# xiao-rp2040.net
KiCad netlist of a schematic drawn in EAGLE
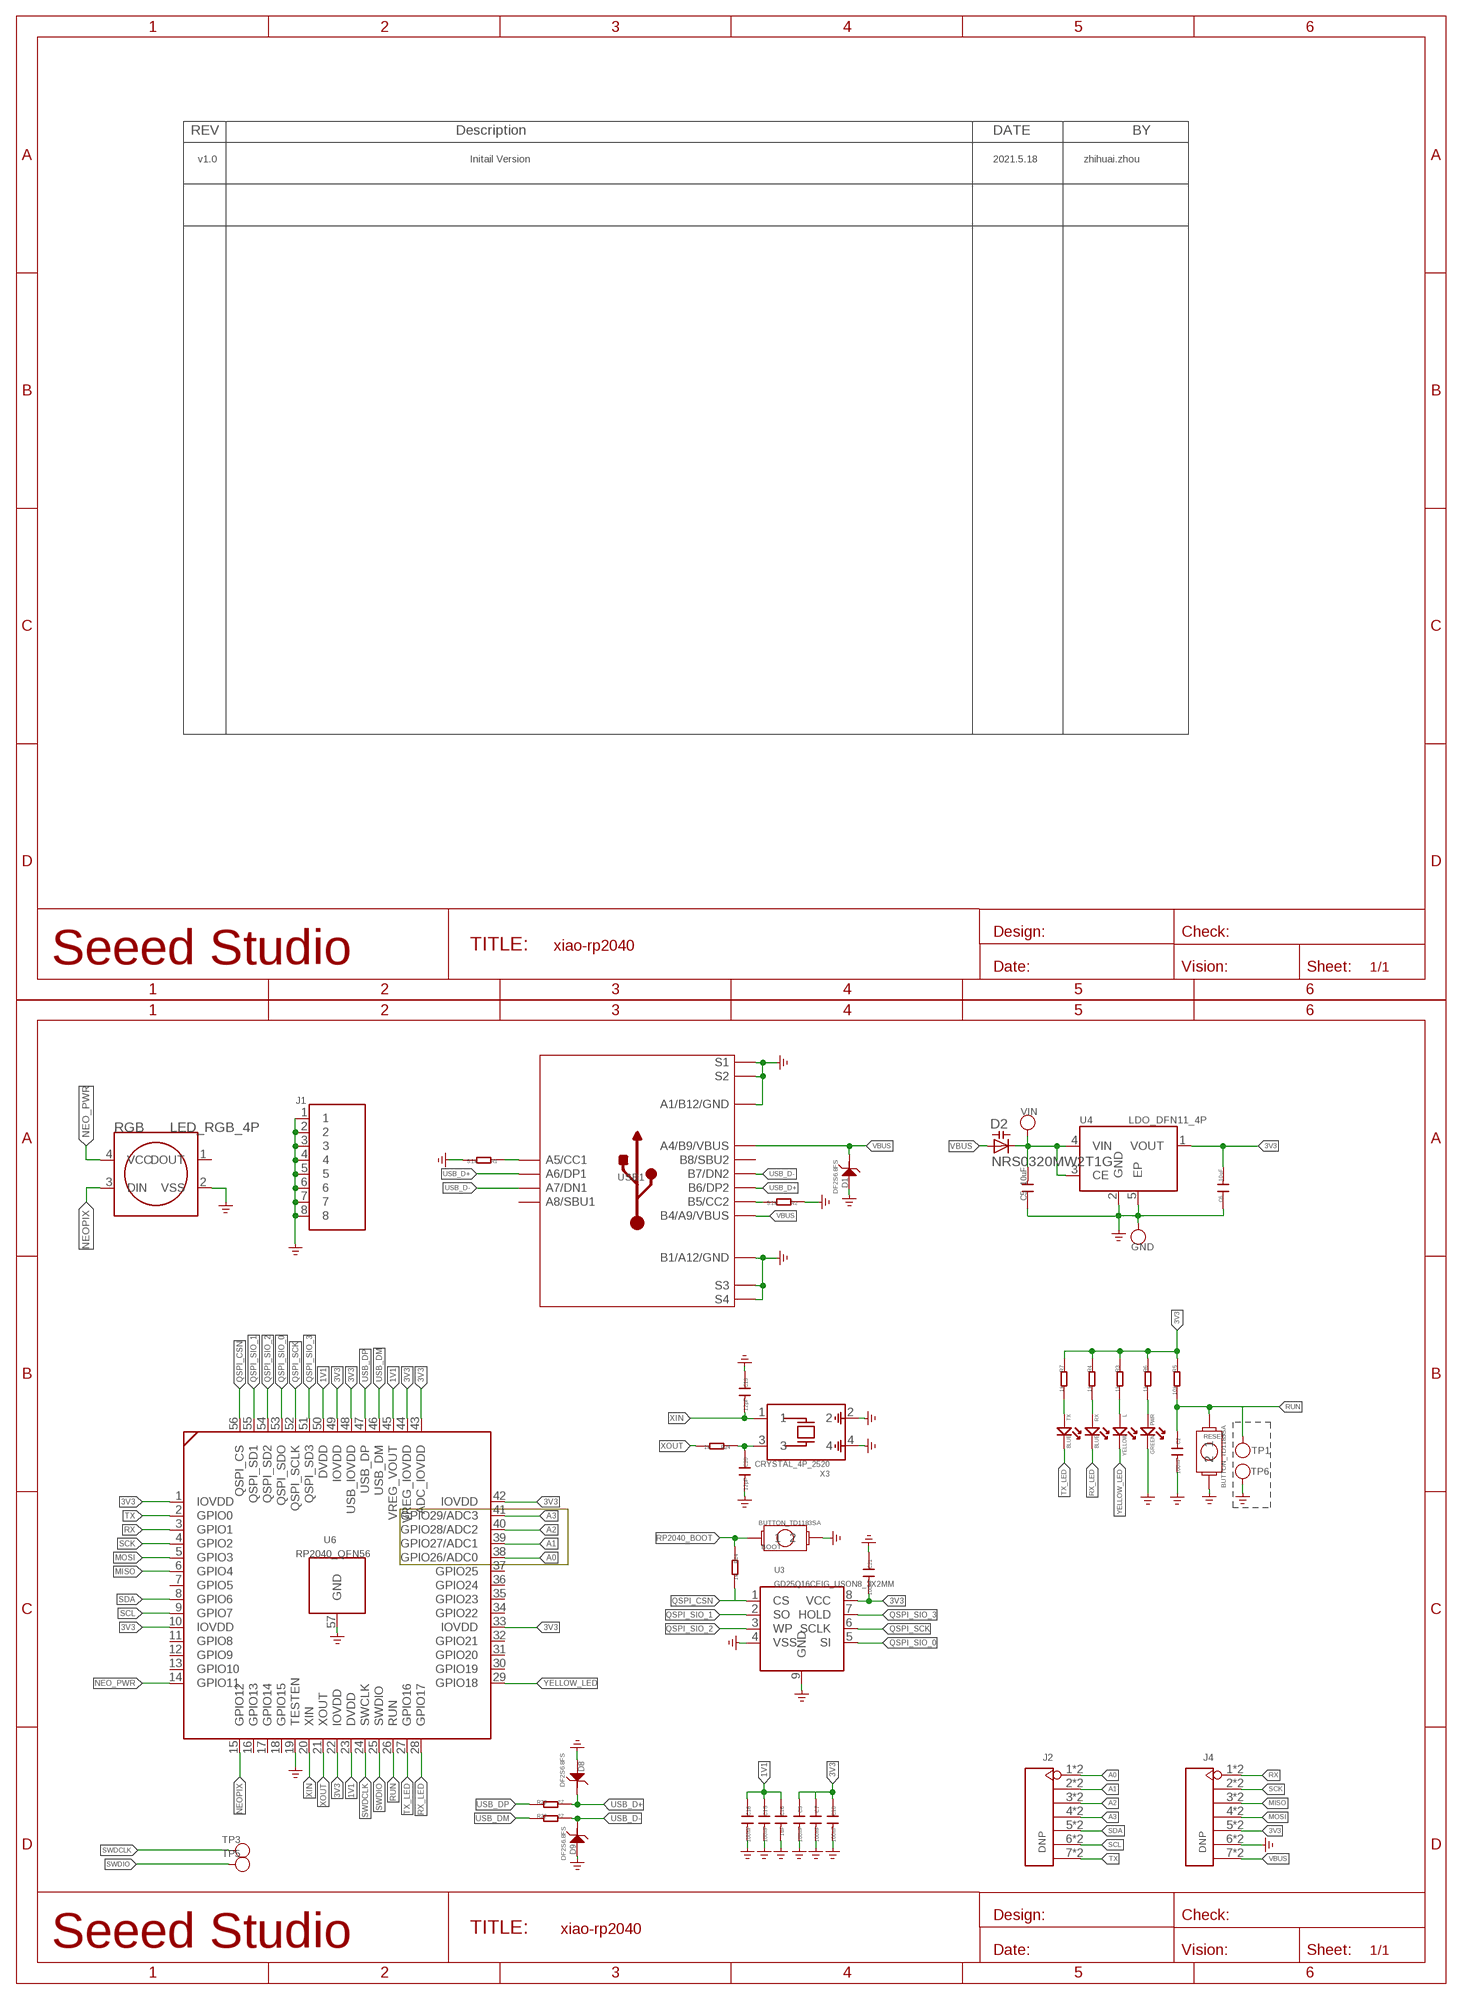
[diagram p0: schematic, sheet 1]

(export (version "E")
  (design (tool "Eeschema 10.0.6"))
  (components
    (comp (ref "BOOT")
      (value "BUTTON_TD1183SA")
      (footprint "eagle-import:BUTTON_TD1183SA")
      (libsource (lib "eagle-import") (part "BUTTON_TD1183SA"))
    )
    (comp (ref "C2")
      (value "100nF")
      (footprint "eagle-import:0201_NORMAL_NOSILK")
      (libsource (lib "eagle-import") (part "CAP{backslash}0201NNS"))
    )
    (comp (ref "C3")
      (value "100nF")
      (footprint "eagle-import:0201_NORMAL_NOSILK")
      (libsource (lib "eagle-import") (part "CAP{backslash}0201NNS"))
    )
    (comp (ref "C5")
      (value "10uF")
      (footprint "eagle-import:C0402")
      (libsource (lib "eagle-import") (part "C-0402"))
    )
    (comp (ref "C6")
      (value "10uF")
      (footprint "eagle-import:C0402")
      (libsource (lib "eagle-import") (part "C-0402"))
    )
    (comp (ref "C7")
      (value "100nF")
      (footprint "eagle-import:0201_NORMAL_NOSILK")
      (libsource (lib "eagle-import") (part "CAP{backslash}0201NNS"))
    )
    (comp (ref "C10")
      (value "100nF")
      (footprint "eagle-import:0201_NORMAL_NOSILK")
      (libsource (lib "eagle-import") (part "CAP{backslash}0201NNS"))
    )
    (comp (ref "C15")
      (value "100nF")
      (footprint "eagle-import:0201_NORMAL_NOSILK")
      (libsource (lib "eagle-import") (part "CAP{backslash}0201NNS"))
    )
    (comp (ref "C16")
      (value "1uF")
      (footprint "eagle-import:0201_NORMAL_NOSILK")
      (libsource (lib "eagle-import") (part "CAP{backslash}0201NNS"))
    )
    (comp (ref "C18")
      (value "100nF")
      (footprint "eagle-import:0201_NORMAL_NOSILK")
      (libsource (lib "eagle-import") (part "CAP{backslash}0201NNS"))
    )
    (comp (ref "C19")
      (value "12pF")
      (footprint "eagle-import:0201_NORMAL_NOSILK")
      (libsource (lib "eagle-import") (part "CAP{backslash}0201NNS"))
    )
    (comp (ref "C20")
      (value "12pF")
      (footprint "eagle-import:0201_NORMAL_NOSILK")
      (libsource (lib "eagle-import") (part "CAP{backslash}0201NNS"))
    )
    (comp (ref "C21")
      (value "100nF")
      (footprint "eagle-import:0201_NORMAL_NOSILK")
      (libsource (lib "eagle-import") (part "CAP{backslash}0201NNS"))
    )
    (comp (ref "D1")
      (value "DF2S6.8FS")
      (footprint "eagle-import:SOD-923")
      (libsource (lib "eagle-import") (part "D-ESD-2P'DF2S6.8FS'"))
    )
    (comp (ref "D2")
      (value "NRS0320MW2T1G")
      (footprint "eagle-import:SOD523")
      (libsource (lib "eagle-import") (part "DIODE_CAPACITANCE-SOD523"))
    )
    (comp (ref "D8")
      (value "DF2S6.8FS")
      (footprint "eagle-import:SOD-923")
      (libsource (lib "eagle-import") (part "D-ESD-2P'DF2S6.8FS'"))
    )
    (comp (ref "D9")
      (value "DF2S6.8FS")
      (footprint "eagle-import:SOD-923")
      (libsource (lib "eagle-import") (part "D-ESD-2P'DF2S6.8FS'"))
    )
    (comp (ref "GND")
      (value "TEST-POINT'4080'")
      (footprint "eagle-import:TP-80X40MIL")
      (libsource (lib "eagle-import") (part "TEST-POINT'4080'"))
    )
    (comp (ref "J1")
      (value "SHIELDING-COVER-XIAO_RP2040_PRD")
      (footprint "eagle-import:SHIELDING-COVER_XIAO_RP2040_PRD")
      (libsource (lib "eagle-import") (part "SHIELDING-COVER-XIAO_RP2040_PRD"))
    )
    (comp (ref "J2")
      (value "DNP")
      (footprint "eagle-import:H7-HALF-HOLE-2.54")
      (libsource (lib "eagle-import") (part "HEADER-7P-HALF-HOLE-2.54"))
    )
    (comp (ref "J4")
      (value "DNP")
      (footprint "eagle-import:H7-HALF-HOLE-2.54")
      (libsource (lib "eagle-import") (part "HEADER-7P-HALF-HOLE-2.54"))
    )
    (comp (ref "L")
      (value "YELLOW")
      (footprint "eagle-import:LED-0402")
      (libsource (lib "eagle-import") (part "LED-0402"))
    )
    (comp (ref "PWR")
      (value "GREEN")
      (footprint "eagle-import:LED-0402")
      (libsource (lib "eagle-import") (part "LED-0402"))
    )
    (comp (ref "R1")
      (value "5.1k")
      (footprint "eagle-import:R0201")
      (libsource (lib "eagle-import") (part "R-0201"))
    )
    (comp (ref "R2")
      (value "5.1k")
      (footprint "eagle-import:R0201")
      (libsource (lib "eagle-import") (part "R-0201"))
    )
    (comp (ref "R3")
      (value "1k")
      (footprint "eagle-import:R0201")
      (libsource (lib "eagle-import") (part "R-0201"))
    )
    (comp (ref "R4")
      (value "1k")
      (footprint "eagle-import:R0201")
      (libsource (lib "eagle-import") (part "R-0201"))
    )
    (comp (ref "R5")
      (value "10k")
      (footprint "eagle-import:R0201")
      (libsource (lib "eagle-import") (part "R-0201"))
    )
    (comp (ref "R6")
      (value "1k")
      (footprint "eagle-import:R0201")
      (libsource (lib "eagle-import") (part "R-0201"))
    )
    (comp (ref "R7")
      (value "1k")
      (footprint "eagle-import:R0201")
      (libsource (lib "eagle-import") (part "R-0201"))
    )
    (comp (ref "R14")
      (value "1k")
      (footprint "eagle-import:R0201")
      (libsource (lib "eagle-import") (part "R-0201"))
    )
    (comp (ref "R22")
      (value "27")
      (footprint "eagle-import:R0201")
      (libsource (lib "eagle-import") (part "R-0201"))
    )
    (comp (ref "R23")
      (value "27")
      (footprint "eagle-import:R0201")
      (libsource (lib "eagle-import") (part "R-0201"))
    )
    (comp (ref "R24")
      (value "1k")
      (footprint "eagle-import:R0201")
      (libsource (lib "eagle-import") (part "R-0201"))
    )
    (comp (ref "RESET")
      (value "BUTTON_TD1183SA")
      (footprint "eagle-import:BUTTON_TD1183SA")
      (libsource (lib "eagle-import") (part "BUTTON_TD1183SA"))
    )
    (comp (ref "RGB")
      (value "LED_RGB_4P")
      (footprint "eagle-import:LED_RGB_2427")
      (libsource (lib "eagle-import") (part "LED_RGB_4P"))
    )
    (comp (ref "RX")
      (value "BLUE")
      (footprint "eagle-import:LED-0402")
      (libsource (lib "eagle-import") (part "LED-0402"))
    )
    (comp (ref "TP1")
      (value "TEST-POINT'4545'")
      (footprint "eagle-import:TP-D45MIL")
      (fields (field (name "PARTNO") "DNP"))
      (libsource (lib "eagle-import") (part "TEST-POINT'4545'"))
    )
    (comp (ref "TP3")
      (value "TEST-POINT'4545'")
      (footprint "eagle-import:TP-D45MIL")
      (fields (field (name "PARTNO") "DNP"))
      (libsource (lib "eagle-import") (part "TEST-POINT'4545'"))
    )
    (comp (ref "TP5")
      (value "TEST-POINT'4545'")
      (footprint "eagle-import:TP-D45MIL")
      (fields (field (name "PARTNO") "DNP"))
      (libsource (lib "eagle-import") (part "TEST-POINT'4545'"))
    )
    (comp (ref "TP6")
      (value "TEST-POINT'4545'")
      (footprint "eagle-import:TP-D45MIL")
      (fields (field (name "PARTNO") "DNP"))
      (libsource (lib "eagle-import") (part "TEST-POINT'4545'"))
    )
    (comp (ref "TX")
      (value "BLUE")
      (footprint "eagle-import:LED-0402")
      (libsource (lib "eagle-import") (part "LED-0402"))
    )
    (comp (ref "U3")
      (value "GD25Q16CEIG_USON8_3X2MM")
      (footprint "eagle-import:GD25Q16CEIG_USON8_3X2MM")
      (libsource (lib "eagle-import") (part "GD25Q16CEIG_USON8_3X2MM"))
    )
    (comp (ref "U4")
      (value "LDO_DFN11_4P")
      (footprint "eagle-import:LDO_DFN1_1_4P")
      (libsource (lib "eagle-import") (part "LDO_DFN11_4P"))
    )
    (comp (ref "U6")
      (value "RP2040_QFN56")
      (footprint "eagle-import:RP2040_QFN56")
      (libsource (lib "eagle-import") (part "RP2040_QFN56"))
    )
    (comp (ref "USB1")
      (value "USB2.0-TYPE-C")
      (footprint "eagle-import:USB2.0-TYPE-C")
      (libsource (lib "eagle-import") (part "USB2.0-TYPE-C"))
    )
    (comp (ref "VIN")
      (value "TEST-POINT'4080'")
      (footprint "eagle-import:TP-80X40MIL")
      (libsource (lib "eagle-import") (part "TEST-POINT'4080'"))
    )
    (comp (ref "X3")
      (value "CRYSTAL_4P_2520")
      (footprint "eagle-import:CRYSTAL_4P_2520")
      (libsource (lib "eagle-import") (part "CRYSTAL_4P_2520"))
    )
  )
  (nets
    (net (code "1") (name "1V1") (class "Default")
      (node (ref "C15") (pin "1") (pinfunction "1_1") (pintype "passive"))
      (node (ref "C16") (pin "1") (pinfunction "1_1") (pintype "passive"))
      (node (ref "C18") (pin "1") (pinfunction "1_1") (pintype "passive"))
      (node (ref "U6") (pin "23") (pinfunction "DVDD_23") (pintype "bidirectional"))
      (node (ref "U6") (pin "45") (pinfunction "VREG_VOUT_45") (pintype "bidirectional"))
      (node (ref "U6") (pin "50") (pinfunction "DVDD_50") (pintype "bidirectional"))
    )
    (net (code "2") (name "3V3") (class "Default")
      (node (ref "C10") (pin "1") (pinfunction "1_1") (pintype "passive"))
      (node (ref "C21") (pin "2") (pinfunction "2_2") (pintype "passive"))
      (node (ref "C3") (pin "1") (pinfunction "1_1") (pintype "passive"))
      (node (ref "C6") (pin "2") (pinfunction "2_2") (pintype "passive"))
      (node (ref "C7") (pin "1") (pinfunction "1_1") (pintype "passive"))
      (node (ref "J4") (pin "17") (pinfunction "5_17") (pintype "bidirectional"))
      (node (ref "J4") (pin "5") (pinfunction "5_5") (pintype "bidirectional"))
      (node (ref "R3") (pin "1") (pinfunction "1_1") (pintype "passive"))
      (node (ref "R4") (pin "1") (pinfunction "1_1") (pintype "passive"))
      (node (ref "R5") (pin "1") (pinfunction "1_1") (pintype "passive"))
      (node (ref "R6") (pin "1") (pinfunction "1_1") (pintype "passive"))
      (node (ref "R7") (pin "1") (pinfunction "1_1") (pintype "passive"))
      (node (ref "U3") (pin "8") (pinfunction "VCC_8") (pintype "bidirectional"))
      (node (ref "U4") (pin "1") (pinfunction "VOUT_1") (pintype "bidirectional"))
      (node (ref "U6") (pin "1") (pinfunction "IOVDD_1") (pintype "bidirectional"))
      (node (ref "U6") (pin "10") (pinfunction "IOVDD_10") (pintype "bidirectional"))
      (node (ref "U6") (pin "22") (pinfunction "IOVDD_22") (pintype "bidirectional"))
      (node (ref "U6") (pin "33") (pinfunction "IOVDD_33") (pintype "bidirectional"))
      (node (ref "U6") (pin "42") (pinfunction "IOVDD_42") (pintype "bidirectional"))
      (node (ref "U6") (pin "43") (pinfunction "ADC_IOVDD_43") (pintype "bidirectional"))
      (node (ref "U6") (pin "44") (pinfunction "VREG_IOVDD_44") (pintype "bidirectional"))
      (node (ref "U6") (pin "48") (pinfunction "USB_IOVDD_48") (pintype "bidirectional"))
      (node (ref "U6") (pin "49") (pinfunction "IOVDD_49") (pintype "bidirectional"))
    )
    (net (code "3") (name "A0") (class "Default")
      (node (ref "J2") (pin "1") (pinfunction "1_1") (pintype "bidirectional"))
      (node (ref "J2") (pin "13") (pinfunction "1_13") (pintype "bidirectional"))
      (node (ref "U6") (pin "38") (pinfunction "GPIO26/ADC0_38") (pintype "bidirectional"))
    )
    (net (code "4") (name "A1") (class "Default")
      (node (ref "J2") (pin "14") (pinfunction "2_14") (pintype "bidirectional"))
      (node (ref "J2") (pin "2") (pinfunction "2_2") (pintype "bidirectional"))
      (node (ref "U6") (pin "39") (pinfunction "GPIO27/ADC1_39") (pintype "bidirectional"))
    )
    (net (code "5") (name "A2") (class "Default")
      (node (ref "J2") (pin "15") (pinfunction "3_15") (pintype "bidirectional"))
      (node (ref "J2") (pin "3") (pinfunction "3_3") (pintype "bidirectional"))
      (node (ref "U6") (pin "40") (pinfunction "GPIO28/ADC2_40") (pintype "bidirectional"))
    )
    (net (code "6") (name "A3") (class "Default")
      (node (ref "J2") (pin "16") (pinfunction "4_16") (pintype "bidirectional"))
      (node (ref "J2") (pin "4") (pinfunction "4_4") (pintype "bidirectional"))
      (node (ref "U6") (pin "41") (pinfunction "GPIO29/ADC3_41") (pintype "bidirectional"))
    )
    (net (code "7") (name "GND_POWER") (class "Default")
      (node (ref "BOOT") (pin "2") (pinfunction "2_2") (pintype "bidirectional"))
      (node (ref "C10") (pin "2") (pinfunction "2_2") (pintype "passive"))
      (node (ref "C15") (pin "2") (pinfunction "2_2") (pintype "passive"))
      (node (ref "C16") (pin "2") (pinfunction "2_2") (pintype "passive"))
      (node (ref "C18") (pin "2") (pinfunction "2_2") (pintype "passive"))
      (node (ref "C19") (pin "1") (pinfunction "1_1") (pintype "passive"))
      (node (ref "C2") (pin "2") (pinfunction "2_2") (pintype "passive"))
      (node (ref "C20") (pin "2") (pinfunction "2_2") (pintype "passive"))
      (node (ref "C21") (pin "1") (pinfunction "1_1") (pintype "passive"))
      (node (ref "C3") (pin "2") (pinfunction "2_2") (pintype "passive"))
      (node (ref "C5") (pin "1") (pinfunction "1_1") (pintype "passive"))
      (node (ref "C6") (pin "1") (pinfunction "1_1") (pintype "passive"))
      (node (ref "C7") (pin "2") (pinfunction "2_2") (pintype "passive"))
      (node (ref "D1") (pin "2") (pinfunction "1_2") (pintype "bidirectional"))
      (node (ref "D8") (pin "2") (pinfunction "1_2") (pintype "bidirectional"))
      (node (ref "D9") (pin "2") (pinfunction "1_2") (pintype "bidirectional"))
      (node (ref "GND") (pin "1") (pinfunction "T_1") (pintype "bidirectional"))
      (node (ref "J1") (pin "1") (pinfunction "1_1") (pintype "bidirectional"))
      (node (ref "J1") (pin "2") (pinfunction "2_2") (pintype "bidirectional"))
      (node (ref "J1") (pin "3") (pinfunction "3_3") (pintype "bidirectional"))
      (node (ref "J1") (pin "4") (pinfunction "4_4") (pintype "bidirectional"))
      (node (ref "J1") (pin "5") (pinfunction "5_5") (pintype "bidirectional"))
      (node (ref "J1") (pin "6") (pinfunction "6_6") (pintype "bidirectional"))
      (node (ref "J1") (pin "7") (pinfunction "7_7") (pintype "bidirectional"))
      (node (ref "J1") (pin "8") (pinfunction "8_8") (pintype "bidirectional"))
      (node (ref "J4") (pin "18") (pinfunction "6_18") (pintype "bidirectional"))
      (node (ref "J4") (pin "6") (pinfunction "6_6") (pintype "bidirectional"))
      (node (ref "PWR") (pin "-") (pinfunction "-_-") (pintype "passive"))
      (node (ref "R1") (pin "2") (pinfunction "2_2") (pintype "passive"))
      (node (ref "R2") (pin "1") (pinfunction "1_1") (pintype "passive"))
      (node (ref "RESET") (pin "2") (pinfunction "2_2") (pintype "bidirectional"))
      (node (ref "RGB") (pin "2") (pinfunction "VSS_2") (pintype "bidirectional"))
      (node (ref "TP6") (pin "T") (pinfunction "T_T") (pintype "bidirectional"))
      (node (ref "U3") (pin "4") (pinfunction "VSS_4") (pintype "bidirectional"))
      (node (ref "U3") (pin "9") (pinfunction "GND_9") (pintype "bidirectional"))
      (node (ref "U4") (pin "2") (pinfunction "GND_2") (pintype "bidirectional"))
      (node (ref "U4") (pin "5") (pinfunction "EP_5") (pintype "bidirectional"))
      (node (ref "U6") (pin "19") (pinfunction "TESTEN_19") (pintype "bidirectional"))
      (node (ref "U6") (pin "57") (pinfunction "GND_57") (pintype "bidirectional"))
      (node (ref "USB1") (pin "A1_B12") (pinfunction "A1/B12/GND_A1_B12") (pintype "bidirectional"))
      (node (ref "USB1") (pin "B1_A12") (pinfunction "B1/A12/GND_B1_A12") (pintype "bidirectional"))
      (node (ref "USB1") (pin "S1") (pinfunction "S1_S1") (pintype "bidirectional"))
      (node (ref "USB1") (pin "S2") (pinfunction "S2_S2") (pintype "bidirectional"))
      (node (ref "USB1") (pin "S3") (pinfunction "S3_S3") (pintype "bidirectional"))
      (node (ref "USB1") (pin "S4") (pinfunction "S4_S4") (pintype "bidirectional"))
      (node (ref "USB1") (pin "S5") (pinfunction "S1_S5") (pintype "bidirectional"))
      (node (ref "USB1") (pin "S6") (pinfunction "S2_S6") (pintype "bidirectional"))
      (node (ref "X3") (pin "2") (pinfunction "2_2") (pintype "bidirectional"))
      (node (ref "X3") (pin "4") (pinfunction "4_4") (pintype "bidirectional"))
    )
    (net (code "8") (name "MISO") (class "Default")
      (node (ref "J4") (pin "15") (pinfunction "3_15") (pintype "bidirectional"))
      (node (ref "J4") (pin "3") (pinfunction "3_3") (pintype "bidirectional"))
      (node (ref "U6") (pin "6") (pinfunction "GPIO4_6") (pintype "bidirectional"))
    )
    (net (code "9") (name "MOSI") (class "Default")
      (node (ref "J4") (pin "16") (pinfunction "4_16") (pintype "bidirectional"))
      (node (ref "J4") (pin "4") (pinfunction "4_4") (pintype "bidirectional"))
      (node (ref "U6") (pin "5") (pinfunction "GPIO3_5") (pintype "bidirectional"))
    )
    (net (code "10") (name "NEOPIX") (class "Default")
      (node (ref "RGB") (pin "3") (pinfunction "DIN_3") (pintype "bidirectional"))
      (node (ref "U6") (pin "15") (pinfunction "GPIO12_15") (pintype "bidirectional"))
    )
    (net (code "11") (name "NEO_PWR") (class "Default")
      (node (ref "RGB") (pin "4") (pinfunction "VCC_4") (pintype "bidirectional"))
      (node (ref "U6") (pin "14") (pinfunction "GPIO11_14") (pintype "bidirectional"))
    )
    (net (code "12") (name "Net-(C20-Pad1)") (class "Default")
      (node (ref "C20") (pin "1") (pinfunction "1_1") (pintype "passive"))
      (node (ref "R24") (pin "1") (pinfunction "1_1") (pintype "passive"))
      (node (ref "X3") (pin "3") (pinfunction "3_3") (pintype "bidirectional"))
    )
    (net (code "13") (name "Net-(L-Pad+)") (class "Default")
      (node (ref "L") (pin "+") (pinfunction "+_+") (pintype "passive"))
      (node (ref "R3") (pin "2") (pinfunction "2_2") (pintype "passive"))
    )
    (net (code "14") (name "Net-(PWR-Pad+)") (class "Default")
      (node (ref "PWR") (pin "+") (pinfunction "+_+") (pintype "passive"))
      (node (ref "R6") (pin "2") (pinfunction "2_2") (pintype "passive"))
    )
    (net (code "15") (name "Net-(R4-Pad2)") (class "Default")
      (node (ref "R4") (pin "2") (pinfunction "2_2") (pintype "passive"))
      (node (ref "RX") (pin "+") (pinfunction "+_+") (pintype "passive"))
    )
    (net (code "16") (name "Net-(R7-Pad2)") (class "Default")
      (node (ref "R7") (pin "2") (pinfunction "2_2") (pintype "passive"))
      (node (ref "TX") (pin "+") (pinfunction "+_+") (pintype "passive"))
    )
    (net (code "17") (name "Net-(U4-CE)") (class "Default")
      (node (ref "C5") (pin "2") (pinfunction "2_2") (pintype "passive"))
      (node (ref "D2") (pin "C") (pinfunction "C_C") (pintype "passive"))
      (node (ref "U4") (pin "3") (pinfunction "CE_3") (pintype "bidirectional"))
      (node (ref "U4") (pin "4") (pinfunction "VIN_4") (pintype "bidirectional"))
      (node (ref "VIN") (pin "1") (pinfunction "T_1") (pintype "bidirectional"))
    )
    (net (code "18") (name "Net-(USB1-A5{slash}CC1)") (class "Default")
      (node (ref "R1") (pin "1") (pinfunction "1_1") (pintype "passive"))
      (node (ref "USB1") (pin "A5") (pinfunction "A5/CC1_A5") (pintype "bidirectional"))
    )
    (net (code "19") (name "Net-(USB1-B5{slash}CC2)") (class "Default")
      (node (ref "R2") (pin "2") (pinfunction "2_2") (pintype "passive"))
      (node (ref "USB1") (pin "B5") (pinfunction "B5/CC2_B5") (pintype "bidirectional"))
    )
    (net (code "20") (name "QSPI_CSN") (class "Default")
      (node (ref "R14") (pin "2") (pinfunction "2_2") (pintype "passive"))
      (node (ref "U3") (pin "1") (pinfunction "CS_1") (pintype "bidirectional"))
      (node (ref "U6") (pin "56") (pinfunction "QSPI_CS_56") (pintype "bidirectional"))
    )
    (net (code "21") (name "QSPI_SCK") (class "Default")
      (node (ref "U3") (pin "6") (pinfunction "SCLK_6") (pintype "bidirectional"))
      (node (ref "U6") (pin "52") (pinfunction "QSPI_SCLK_52") (pintype "bidirectional"))
    )
    (net (code "22") (name "QSPI_SIO_0") (class "Default")
      (node (ref "U3") (pin "5") (pinfunction "SI_5") (pintype "bidirectional"))
      (node (ref "U6") (pin "53") (pinfunction "QSPI_SDO_53") (pintype "bidirectional"))
    )
    (net (code "23") (name "QSPI_SIO_1") (class "Default")
      (node (ref "U3") (pin "2") (pinfunction "SO_2") (pintype "bidirectional"))
      (node (ref "U6") (pin "55") (pinfunction "QSPI_SD1_55") (pintype "bidirectional"))
    )
    (net (code "24") (name "QSPI_SIO_2") (class "Default")
      (node (ref "U3") (pin "3") (pinfunction "WP_3") (pintype "bidirectional"))
      (node (ref "U6") (pin "54") (pinfunction "QSPI_SD2_54") (pintype "bidirectional"))
    )
    (net (code "25") (name "QSPI_SIO_3") (class "Default")
      (node (ref "U3") (pin "7") (pinfunction "HOLD_7") (pintype "bidirectional"))
      (node (ref "U6") (pin "51") (pinfunction "QSPI_SD3_51") (pintype "bidirectional"))
    )
    (net (code "26") (name "RP2040_BOOT") (class "Default")
      (node (ref "BOOT") (pin "1") (pinfunction "1_1") (pintype "bidirectional"))
      (node (ref "R14") (pin "1") (pinfunction "1_1") (pintype "passive"))
    )
    (net (code "27") (name "RUN") (class "Default")
      (node (ref "C2") (pin "1") (pinfunction "1_1") (pintype "passive"))
      (node (ref "R5") (pin "2") (pinfunction "2_2") (pintype "passive"))
      (node (ref "RESET") (pin "1") (pinfunction "1_1") (pintype "bidirectional"))
      (node (ref "TP1") (pin "T") (pinfunction "T_T") (pintype "bidirectional"))
      (node (ref "U6") (pin "26") (pinfunction "RUN_26") (pintype "bidirectional"))
    )
    (net (code "28") (name "RX") (class "Default")
      (node (ref "J4") (pin "1") (pinfunction "1_1") (pintype "bidirectional"))
      (node (ref "J4") (pin "13") (pinfunction "1_13") (pintype "bidirectional"))
      (node (ref "U6") (pin "3") (pinfunction "GPIO1_3") (pintype "bidirectional"))
    )
    (net (code "29") (name "RX_LED") (class "Default")
      (node (ref "RX") (pin "-") (pinfunction "-_-") (pintype "passive"))
      (node (ref "U6") (pin "28") (pinfunction "GPIO17_28") (pintype "bidirectional"))
    )
    (net (code "30") (name "SCK") (class "Default")
      (node (ref "J4") (pin "14") (pinfunction "2_14") (pintype "bidirectional"))
      (node (ref "J4") (pin "2") (pinfunction "2_2") (pintype "bidirectional"))
      (node (ref "U6") (pin "4") (pinfunction "GPIO2_4") (pintype "bidirectional"))
    )
    (net (code "31") (name "SCL") (class "Default")
      (node (ref "J2") (pin "18") (pinfunction "6_18") (pintype "bidirectional"))
      (node (ref "J2") (pin "6") (pinfunction "6_6") (pintype "bidirectional"))
      (node (ref "U6") (pin "9") (pinfunction "GPIO7_9") (pintype "bidirectional"))
    )
    (net (code "32") (name "SDA") (class "Default")
      (node (ref "J2") (pin "17") (pinfunction "5_17") (pintype "bidirectional"))
      (node (ref "J2") (pin "5") (pinfunction "5_5") (pintype "bidirectional"))
      (node (ref "U6") (pin "8") (pinfunction "GPIO6_8") (pintype "bidirectional"))
    )
    (net (code "33") (name "SWDCLK") (class "Default")
      (node (ref "TP3") (pin "T") (pinfunction "T_T") (pintype "bidirectional"))
      (node (ref "U6") (pin "24") (pinfunction "SWCLK_24") (pintype "bidirectional"))
    )
    (net (code "34") (name "SWDIO") (class "Default")
      (node (ref "TP5") (pin "T") (pinfunction "T_T") (pintype "bidirectional"))
      (node (ref "U6") (pin "25") (pinfunction "SWDIO_25") (pintype "bidirectional"))
    )
    (net (code "35") (name "TX") (class "Default")
      (node (ref "J2") (pin "19") (pinfunction "7_19") (pintype "bidirectional"))
      (node (ref "J2") (pin "7") (pinfunction "7_7") (pintype "bidirectional"))
      (node (ref "U6") (pin "2") (pinfunction "GPIO0_2") (pintype "bidirectional"))
    )
    (net (code "36") (name "TX_LED") (class "Default")
      (node (ref "TX") (pin "-") (pinfunction "-_-") (pintype "passive"))
      (node (ref "U6") (pin "27") (pinfunction "GPIO16_27") (pintype "bidirectional"))
    )
    (net (code "37") (name "USB_D+") (class "Default")
      (node (ref "D8") (pin "1") (pinfunction "2_1") (pintype "bidirectional"))
      (node (ref "R23") (pin "2") (pinfunction "2_2") (pintype "passive"))
      (node (ref "USB1") (pin "A6") (pinfunction "A6/DP1_A6") (pintype "bidirectional"))
      (node (ref "USB1") (pin "B6") (pinfunction "B6/DP2_B6") (pintype "bidirectional"))
    )
    (net (code "38") (name "USB_D-") (class "Default")
      (node (ref "D9") (pin "1") (pinfunction "2_1") (pintype "bidirectional"))
      (node (ref "R22") (pin "2") (pinfunction "2_2") (pintype "passive"))
      (node (ref "USB1") (pin "A7") (pinfunction "A7/DN1_A7") (pintype "bidirectional"))
      (node (ref "USB1") (pin "B7") (pinfunction "B7/DN2_B7") (pintype "bidirectional"))
    )
    (net (code "39") (name "USB_DM") (class "Default")
      (node (ref "R22") (pin "1") (pinfunction "1_1") (pintype "passive"))
      (node (ref "U6") (pin "46") (pinfunction "USB_DM_46") (pintype "bidirectional"))
    )
    (net (code "40") (name "USB_DP") (class "Default")
      (node (ref "R23") (pin "1") (pinfunction "1_1") (pintype "passive"))
      (node (ref "U6") (pin "47") (pinfunction "USB_DP_47") (pintype "bidirectional"))
    )
    (net (code "41") (name "VBUS") (class "Default")
      (node (ref "D1") (pin "1") (pinfunction "2_1") (pintype "bidirectional"))
      (node (ref "D2") (pin "A") (pinfunction "A_A") (pintype "passive"))
      (node (ref "J4") (pin "19") (pinfunction "7_19") (pintype "bidirectional"))
      (node (ref "J4") (pin "7") (pinfunction "7_7") (pintype "bidirectional"))
      (node (ref "USB1") (pin "A4_B9") (pinfunction "A4/B9/VBUS_A4_B9") (pintype "bidirectional"))
      (node (ref "USB1") (pin "B4_A9") (pinfunction "B4/A9/VBUS_B4_A9") (pintype "bidirectional"))
    )
    (net (code "42") (name "XIN") (class "Default")
      (node (ref "C19") (pin "2") (pinfunction "2_2") (pintype "passive"))
      (node (ref "U6") (pin "20") (pinfunction "XIN_20") (pintype "bidirectional"))
      (node (ref "X3") (pin "1") (pinfunction "1_1") (pintype "bidirectional"))
    )
    (net (code "43") (name "XOUT") (class "Default")
      (node (ref "R24") (pin "2") (pinfunction "2_2") (pintype "passive"))
      (node (ref "U6") (pin "21") (pinfunction "XOUT_21") (pintype "bidirectional"))
    )
    (net (code "44") (name "YELLOW_LED") (class "Default")
      (node (ref "L") (pin "-") (pinfunction "-_-") (pintype "passive"))
      (node (ref "U6") (pin "29") (pinfunction "GPIO18_29") (pintype "bidirectional"))
    )
    (net (code "45") (name "unconnected-(RGB-DOUT-Pad1)") (class "Default")
      (node (ref "RGB") (pin "1") (pinfunction "DOUT_1") (pintype "bidirectional"))
    )
    (net (code "46") (name "unconnected-(U6-GPIO5-Pad7)") (class "Default")
      (node (ref "U6") (pin "7") (pinfunction "GPIO5_7") (pintype "bidirectional"))
    )
    (net (code "47") (name "unconnected-(U6-GPIO8-Pad11)") (class "Default")
      (node (ref "U6") (pin "11") (pinfunction "GPIO8_11") (pintype "bidirectional"))
    )
    (net (code "48") (name "unconnected-(U6-GPIO9-Pad12)") (class "Default")
      (node (ref "U6") (pin "12") (pinfunction "GPIO9_12") (pintype "bidirectional"))
    )
    (net (code "49") (name "unconnected-(U6-GPIO10-Pad13)") (class "Default")
      (node (ref "U6") (pin "13") (pinfunction "GPIO10_13") (pintype "bidirectional"))
    )
    (net (code "50") (name "unconnected-(U6-GPIO13-Pad16)") (class "Default")
      (node (ref "U6") (pin "16") (pinfunction "GPIO13_16") (pintype "bidirectional"))
    )
    (net (code "51") (name "unconnected-(U6-GPIO14-Pad17)") (class "Default")
      (node (ref "U6") (pin "17") (pinfunction "GPIO14_17") (pintype "bidirectional"))
    )
    (net (code "52") (name "unconnected-(U6-GPIO15-Pad18)") (class "Default")
      (node (ref "U6") (pin "18") (pinfunction "GPIO15_18") (pintype "bidirectional"))
    )
    (net (code "53") (name "unconnected-(U6-GPIO19-Pad30)") (class "Default")
      (node (ref "U6") (pin "30") (pinfunction "GPIO19_30") (pintype "bidirectional"))
    )
    (net (code "54") (name "unconnected-(U6-GPIO20-Pad31)") (class "Default")
      (node (ref "U6") (pin "31") (pinfunction "GPIO20_31") (pintype "bidirectional"))
    )
    (net (code "55") (name "unconnected-(U6-GPIO21-Pad32)") (class "Default")
      (node (ref "U6") (pin "32") (pinfunction "GPIO21_32") (pintype "bidirectional"))
    )
    (net (code "56") (name "unconnected-(U6-GPIO22-Pad34)") (class "Default")
      (node (ref "U6") (pin "34") (pinfunction "GPIO22_34") (pintype "bidirectional"))
    )
    (net (code "57") (name "unconnected-(U6-GPIO23-Pad35)") (class "Default")
      (node (ref "U6") (pin "35") (pinfunction "GPIO23_35") (pintype "bidirectional"))
    )
    (net (code "58") (name "unconnected-(U6-GPIO24-Pad36)") (class "Default")
      (node (ref "U6") (pin "36") (pinfunction "GPIO24_36") (pintype "bidirectional"))
    )
    (net (code "59") (name "unconnected-(U6-GPIO25-Pad37)") (class "Default")
      (node (ref "U6") (pin "37") (pinfunction "GPIO25_37") (pintype "bidirectional"))
    )
    (net (code "60") (name "unconnected-(USB1-A8{slash}SBU1-PadA8)") (class "Default")
      (node (ref "USB1") (pin "A8") (pinfunction "A8/SBU1_A8") (pintype "bidirectional"))
    )
    (net (code "61") (name "unconnected-(USB1-B8{slash}SBU2-PadB8)") (class "Default")
      (node (ref "USB1") (pin "B8") (pinfunction "B8/SBU2_B8") (pintype "bidirectional"))
    )
  )
)
